# 2_RELAY.net
KiCad netlist of a schematic drawn in Altium Designer
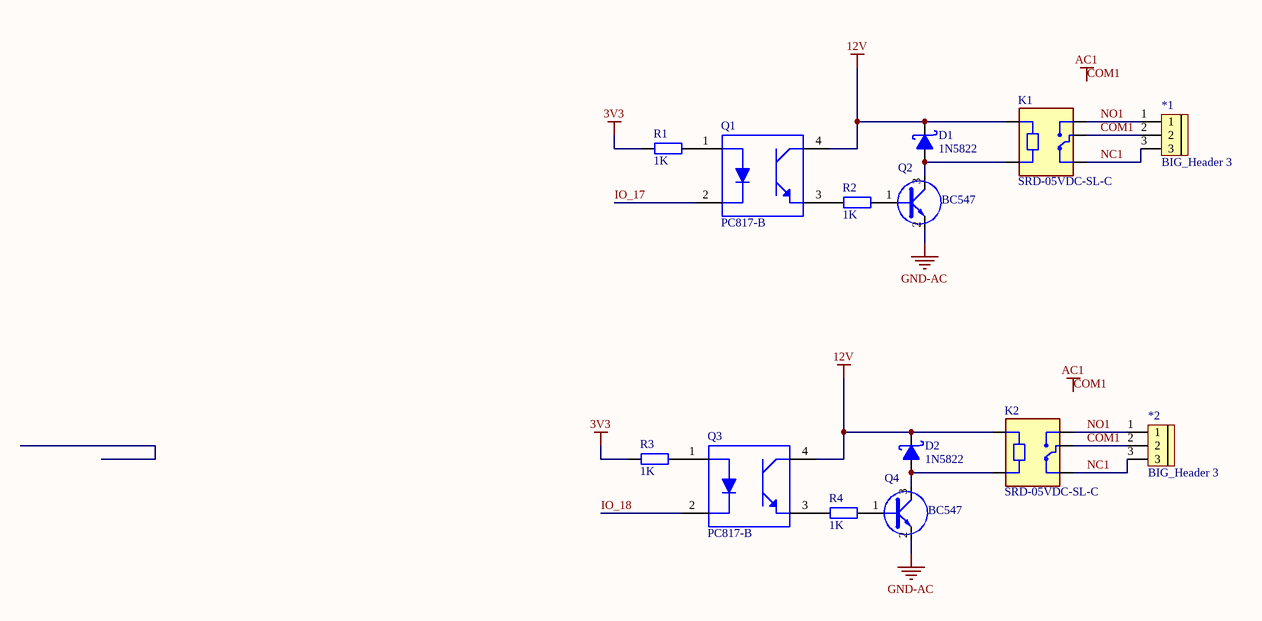
[diagram p0: 2.RELAY.SchDoc]

(export (version "E")
  (design (tool "Eeschema 10.0.6"))
  (components
    (comp (ref "*1")
      (value "BIG_Header 3")
      (footprint "KF-128_3P")
      (libsource (lib "Main") (part "BIG_Header 3"))
    )
    (comp (ref "*2")
      (value "BIG_Header 3")
      (footprint "KF-128_3P")
      (libsource (lib "Main") (part "BIG_Header 3"))
    )
    (comp (ref "D1")
      (value "1N5822")
      (footprint "SMA")
      (description "Schottky Rectifiers")
      (libsource (lib "Main") (part "1N5822"))
    )
    (comp (ref "D2")
      (value "1N5822")
      (footprint "SMA")
      (description "Schottky Rectifiers")
      (libsource (lib "Main") (part "1N5822"))
    )
    (comp (ref "K1")
      (value "SRD-05VDC-SL-C")
      (footprint "RELAY_SRD-05VDC-SL-C")
      (description "https://linhkien.cxt.vn/3210-sra-12vdc-cl-songle-relay-20a-12vdc-5-chan.html")
      (fields (field (name "MF") "Songle Relay"))
      (libsource (lib "SRD-05VDC-SL-C") (part "SRD-05VDC-SL-C"))
    )
    (comp (ref "K2")
      (value "SRD-05VDC-SL-C")
      (footprint "RELAY_SRD-05VDC-SL-C")
      (description "https://linhkien.cxt.vn/3210-sra-12vdc-cl-songle-relay-20a-12vdc-5-chan.html")
      (fields (field (name "MF") "Songle Relay"))
      (libsource (lib "SRD-05VDC-SL-C") (part "SRD-05VDC-SL-C"))
    )
    (comp (ref "Q1")
      (value "PC817-B")
      (footprint "DIP762W50P254L650H455Q4B")
      (description "Phototransistors 4-DIP _0.300, 7.62mm_")
      (fields (field (name "MF") "American Bright"))
      (libsource (lib "PC817-B") (part "PC817-B"))
    )
    (comp (ref "Q2")
      (value "BC547")
      (footprint "TO-92")
      (description "NPN 600mW, ECB")
      (libsource (lib "Main") (part "C1815"))
    )
    (comp (ref "Q3")
      (value "PC817-B")
      (footprint "DIP762W50P254L650H455Q4B")
      (description "Phototransistors 4-DIP _0.300, 7.62mm_")
      (fields (field (name "MF") "American Bright"))
      (libsource (lib "PC817-B") (part "PC817-B"))
    )
    (comp (ref "Q4")
      (value "BC547")
      (footprint "TO-92")
      (description "NPN 600mW, ECB")
      (libsource (lib "Main") (part "C1815"))
    )
    (comp (ref "R1")
      (value "1K")
      (footprint "RES-SMD-0805")
      (description "Resistor SMD")
      (fields
        (field (name "MANUFACTURER") "Generic Components")
        (field (name "PUBLISHER") "Altium Hobart Technology Centre")
      )
      (libsource (lib "Main") (part "Resistor - SMD"))
    )
    (comp (ref "R2")
      (value "1K")
      (footprint "RES-SMD-0805")
      (description "Resistor SMD")
      (fields
        (field (name "MANUFACTURER") "Generic Components")
        (field (name "PUBLISHER") "Altium Hobart Technology Centre")
      )
      (libsource (lib "Main") (part "Resistor - SMD"))
    )
    (comp (ref "R3")
      (value "1K")
      (footprint "RES-SMD-0805")
      (description "Resistor SMD")
      (fields
        (field (name "MANUFACTURER") "Generic Components")
        (field (name "PUBLISHER") "Altium Hobart Technology Centre")
      )
      (libsource (lib "Main") (part "Resistor - SMD"))
    )
    (comp (ref "R4")
      (value "1K")
      (footprint "RES-SMD-0805")
      (description "Resistor SMD")
      (fields
        (field (name "MANUFACTURER") "Generic Components")
        (field (name "PUBLISHER") "Altium Hobart Technology Centre")
      )
      (libsource (lib "Main") (part "Resistor - SMD"))
    )
  )
  (nets
    (net (code "1") (name "/IO_17") (class "Default")
      (node (ref "Q1") (pin "2") (pinfunction "CATHODE_2") (pintype "passive"))
    )
    (net (code "2") (name "/IO_18") (class "Default")
      (node (ref "Q3") (pin "2") (pinfunction "CATHODE_2") (pintype "passive"))
    )
    (net (code "3") (name "/NC1") (class "Default")
      (node (ref "*1") (pin "3") (pinfunction "3_3") (pintype "passive"))
      (node (ref "*2") (pin "3") (pinfunction "3_3") (pintype "passive"))
      (node (ref "K1") (pin "NC") (pinfunction "NC_NC") (pintype "passive"))
      (node (ref "K2") (pin "NC") (pinfunction "NC_NC") (pintype "passive"))
    )
    (net (code "4") (name "/NO1") (class "Default")
      (node (ref "*1") (pin "1") (pinfunction "1_1") (pintype "passive"))
      (node (ref "*2") (pin "1") (pinfunction "1_1") (pintype "passive"))
      (node (ref "K1") (pin "NO") (pinfunction "NO_NO") (pintype "passive"))
      (node (ref "K2") (pin "NO") (pinfunction "NO_NO") (pintype "passive"))
    )
    (net (code "5") (name "3V3") (class "Default")
      (node (ref "R1") (pin "2") (pinfunction "2_2") (pintype "passive"))
      (node (ref "R3") (pin "2") (pinfunction "2_2") (pintype "passive"))
    )
    (net (code "6") (name "12V") (class "Default")
      (node (ref "D1") (pin "2") (pinfunction "K_2") (pintype "passive"))
      (node (ref "D2") (pin "2") (pinfunction "K_2") (pintype "passive"))
      (node (ref "K1") (pin "A1") (pinfunction "A1_A1") (pintype "passive"))
      (node (ref "K2") (pin "A1") (pinfunction "A1_A1") (pintype "passive"))
      (node (ref "Q1") (pin "4") (pinfunction "COLLECTOR_4") (pintype "passive"))
      (node (ref "Q3") (pin "4") (pinfunction "COLLECTOR_4") (pintype "passive"))
    )
    (net (code "7") (name "AC1") (class "Default")
      (node (ref "*1") (pin "2") (pinfunction "2_2") (pintype "passive"))
      (node (ref "*2") (pin "2") (pinfunction "2_2") (pintype "passive"))
      (node (ref "K1") (pin "COM") (pinfunction "COM_COM") (pintype "passive"))
      (node (ref "K2") (pin "COM") (pinfunction "COM_COM") (pintype "passive"))
    )
    (net (code "8") (name "GND-AC") (class "Default")
      (node (ref "Q2") (pin "2") (pinfunction "E_2") (pintype "passive"))
      (node (ref "Q4") (pin "2") (pinfunction "E_2") (pintype "passive"))
    )
    (net (code "9") (name "Net-(D1-A)") (class "Default")
      (node (ref "D1") (pin "1") (pinfunction "A_1") (pintype "passive"))
      (node (ref "K1") (pin "A2") (pinfunction "A2_A2") (pintype "passive"))
      (node (ref "Q2") (pin "3") (pinfunction "C_3") (pintype "passive"))
    )
    (net (code "10") (name "Net-(D2-A)") (class "Default")
      (node (ref "D2") (pin "1") (pinfunction "A_1") (pintype "passive"))
      (node (ref "K2") (pin "A2") (pinfunction "A2_A2") (pintype "passive"))
      (node (ref "Q4") (pin "3") (pinfunction "C_3") (pintype "passive"))
    )
    (net (code "11") (name "Net-(Q1-ANODE)") (class "Default")
      (node (ref "Q1") (pin "1") (pinfunction "ANODE_1") (pintype "passive"))
      (node (ref "R1") (pin "1") (pinfunction "1_1") (pintype "passive"))
    )
    (net (code "12") (name "Net-(Q1-EMITTER)") (class "Default")
      (node (ref "Q1") (pin "3") (pinfunction "EMITTER_3") (pintype "passive"))
      (node (ref "R2") (pin "2") (pinfunction "2_2") (pintype "passive"))
    )
    (net (code "13") (name "Net-(Q2-B)") (class "Default")
      (node (ref "Q2") (pin "1") (pinfunction "B_1") (pintype "passive"))
      (node (ref "R2") (pin "1") (pinfunction "1_1") (pintype "passive"))
    )
    (net (code "14") (name "Net-(Q3-ANODE)") (class "Default")
      (node (ref "Q3") (pin "1") (pinfunction "ANODE_1") (pintype "passive"))
      (node (ref "R3") (pin "1") (pinfunction "1_1") (pintype "passive"))
    )
    (net (code "15") (name "Net-(Q3-EMITTER)") (class "Default")
      (node (ref "Q3") (pin "3") (pinfunction "EMITTER_3") (pintype "passive"))
      (node (ref "R4") (pin "2") (pinfunction "2_2") (pintype "passive"))
    )
    (net (code "16") (name "Net-(Q4-B)") (class "Default")
      (node (ref "Q4") (pin "1") (pinfunction "B_1") (pintype "passive"))
      (node (ref "R4") (pin "1") (pinfunction "1_1") (pintype "passive"))
    )
  )
)
